# 03_-_28PINS_SCHEMATIC.net
KiCad netlist of a schematic drawn in Altium Designer
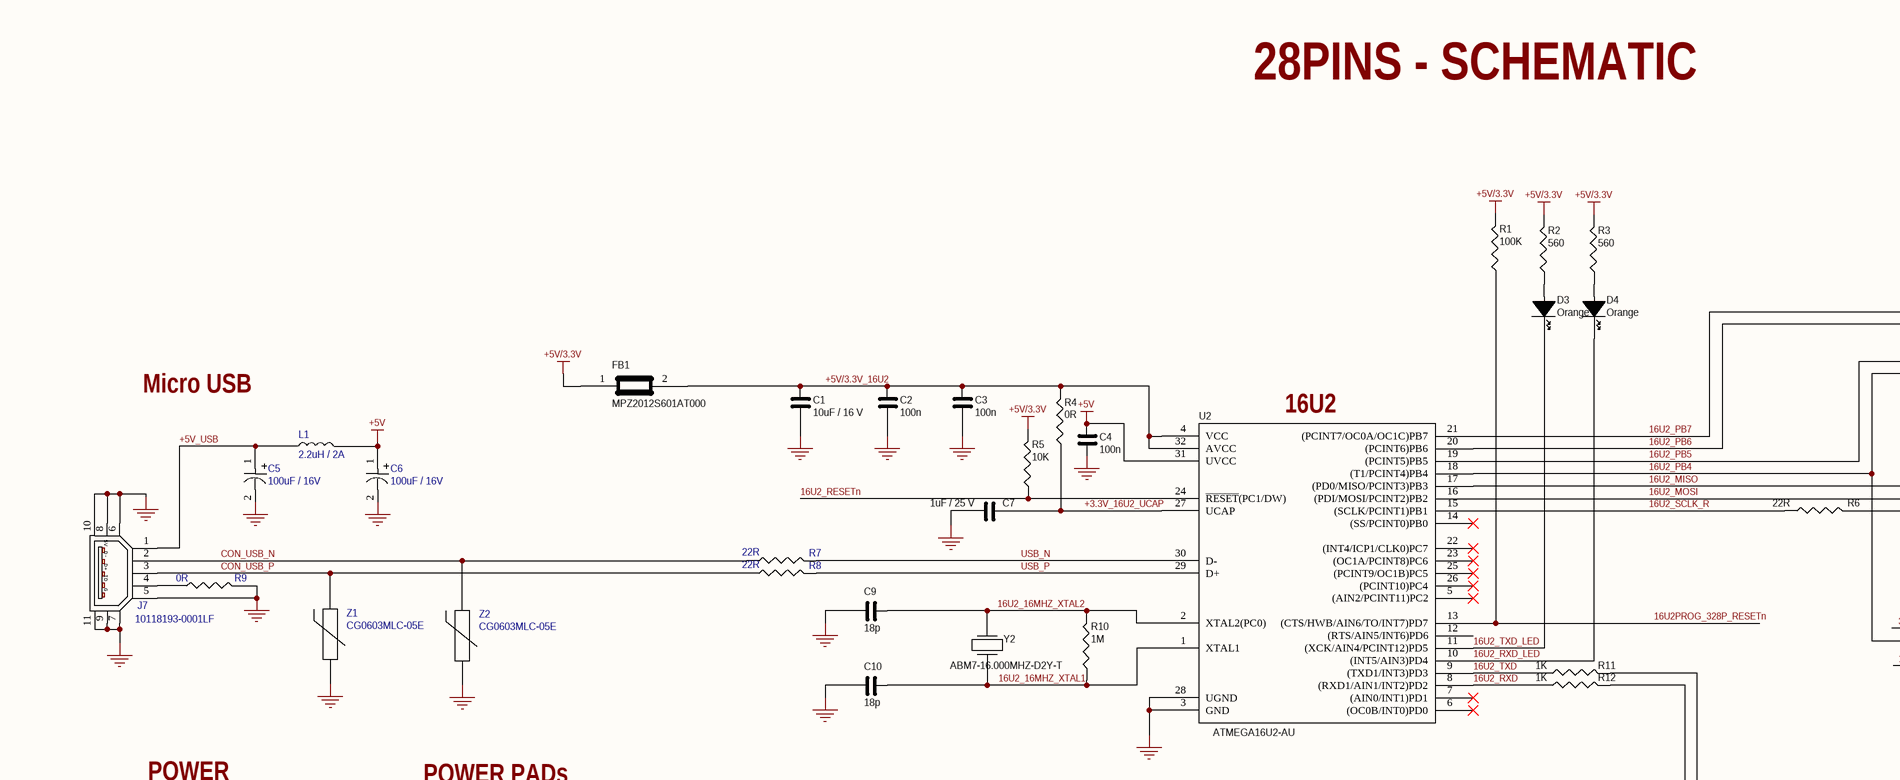
[diagram p0: [03] - 28PINS SCHEMATIC.SchDoc, top left]
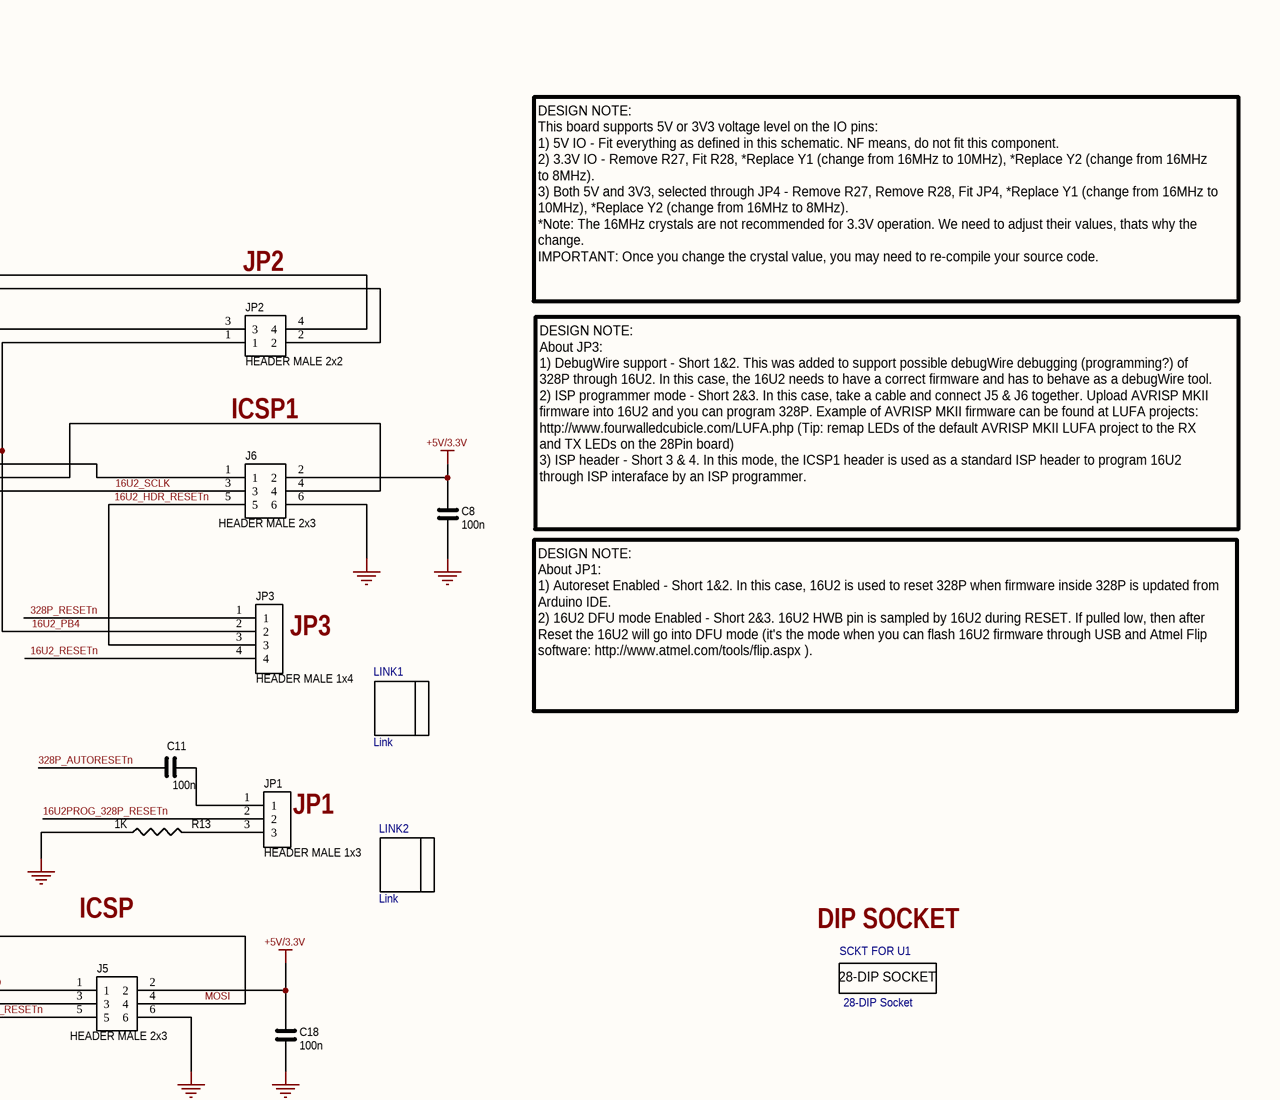
[diagram p1: [03] - 28PINS SCHEMATIC.SchDoc, top right]
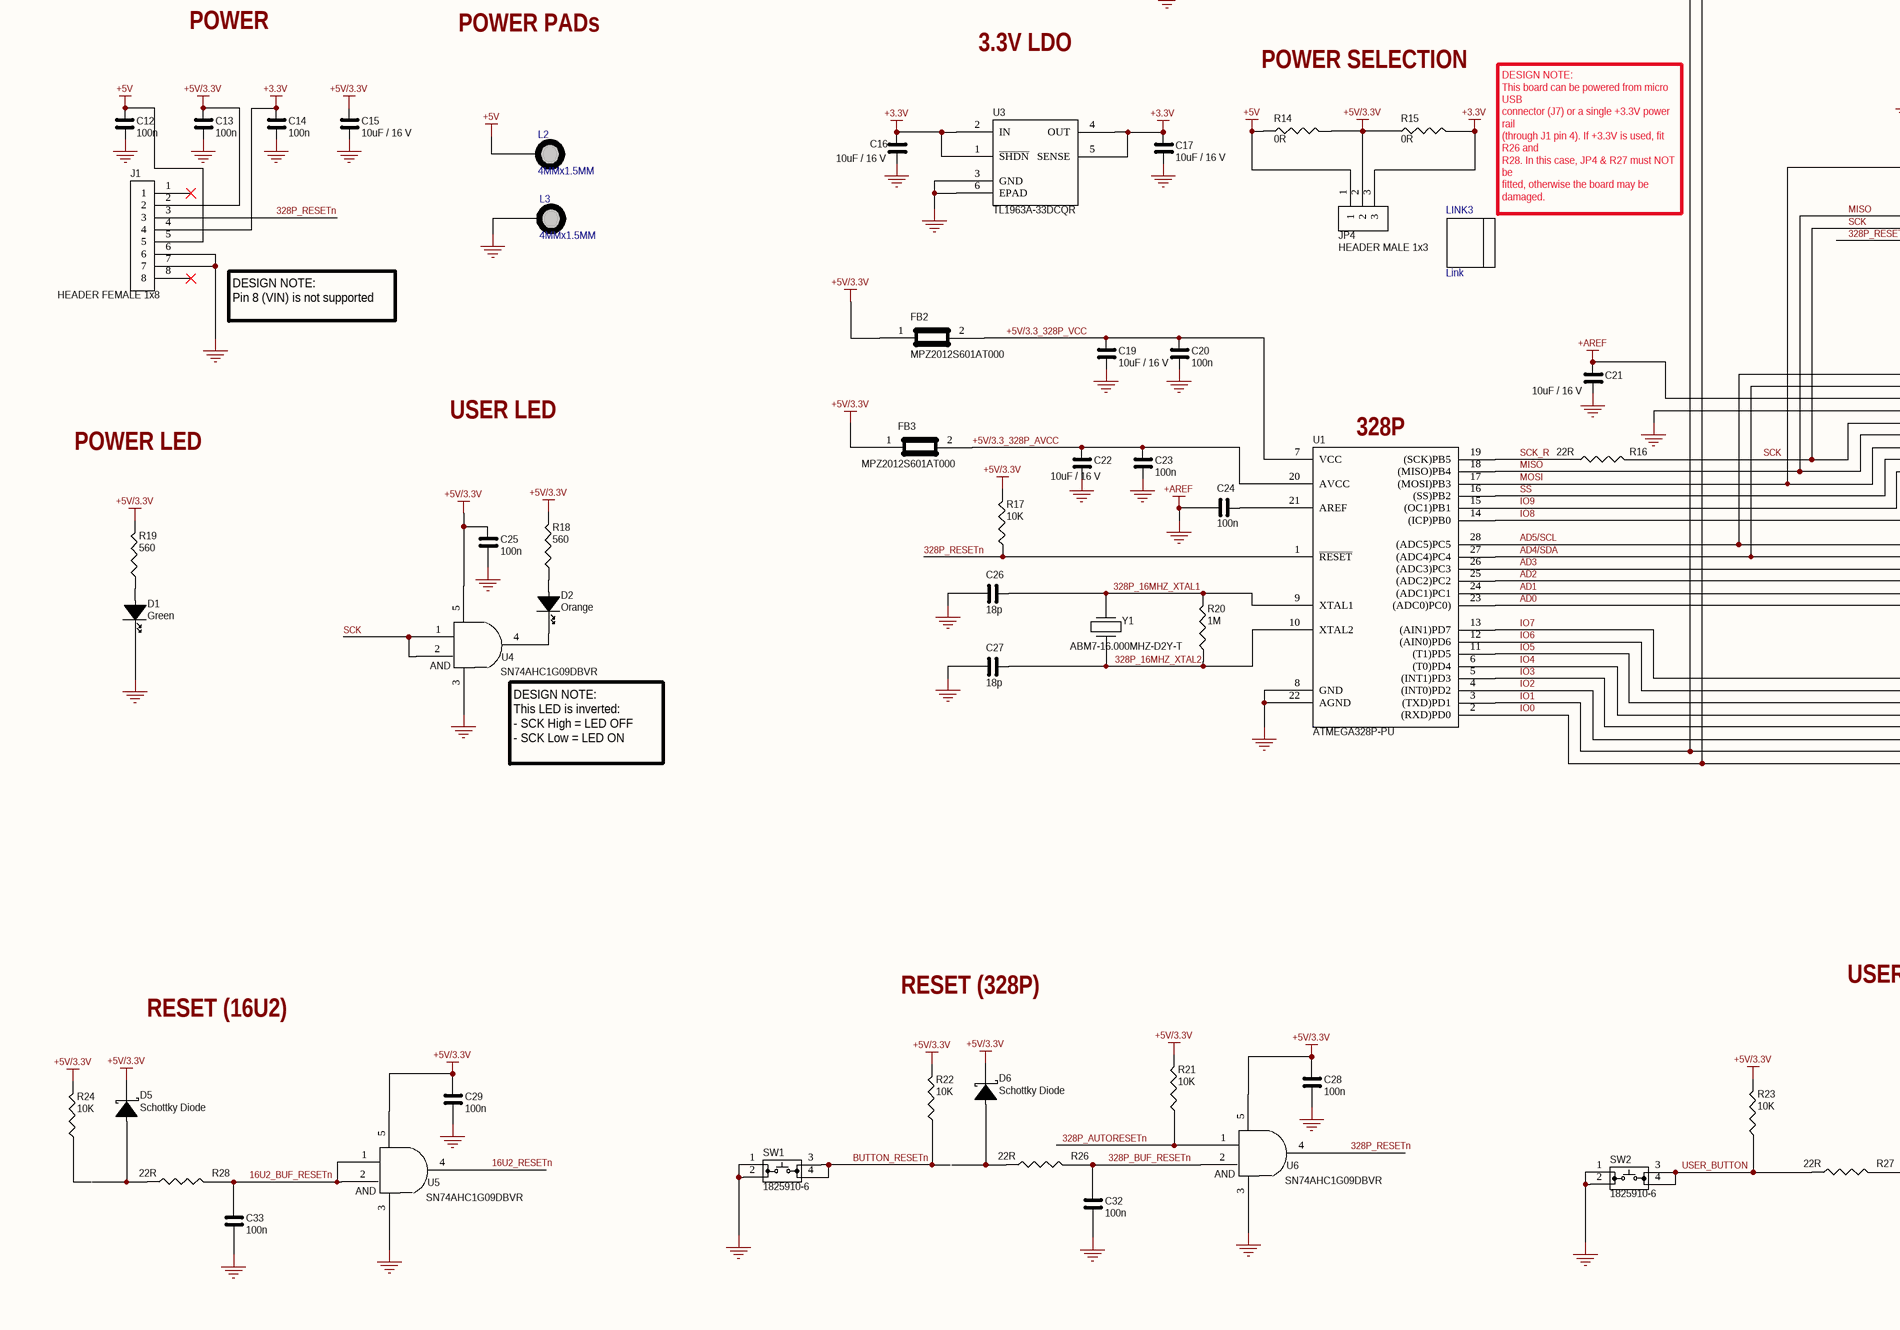
[diagram p2: [03] - 28PINS SCHEMATIC.SchDoc, bottom left]
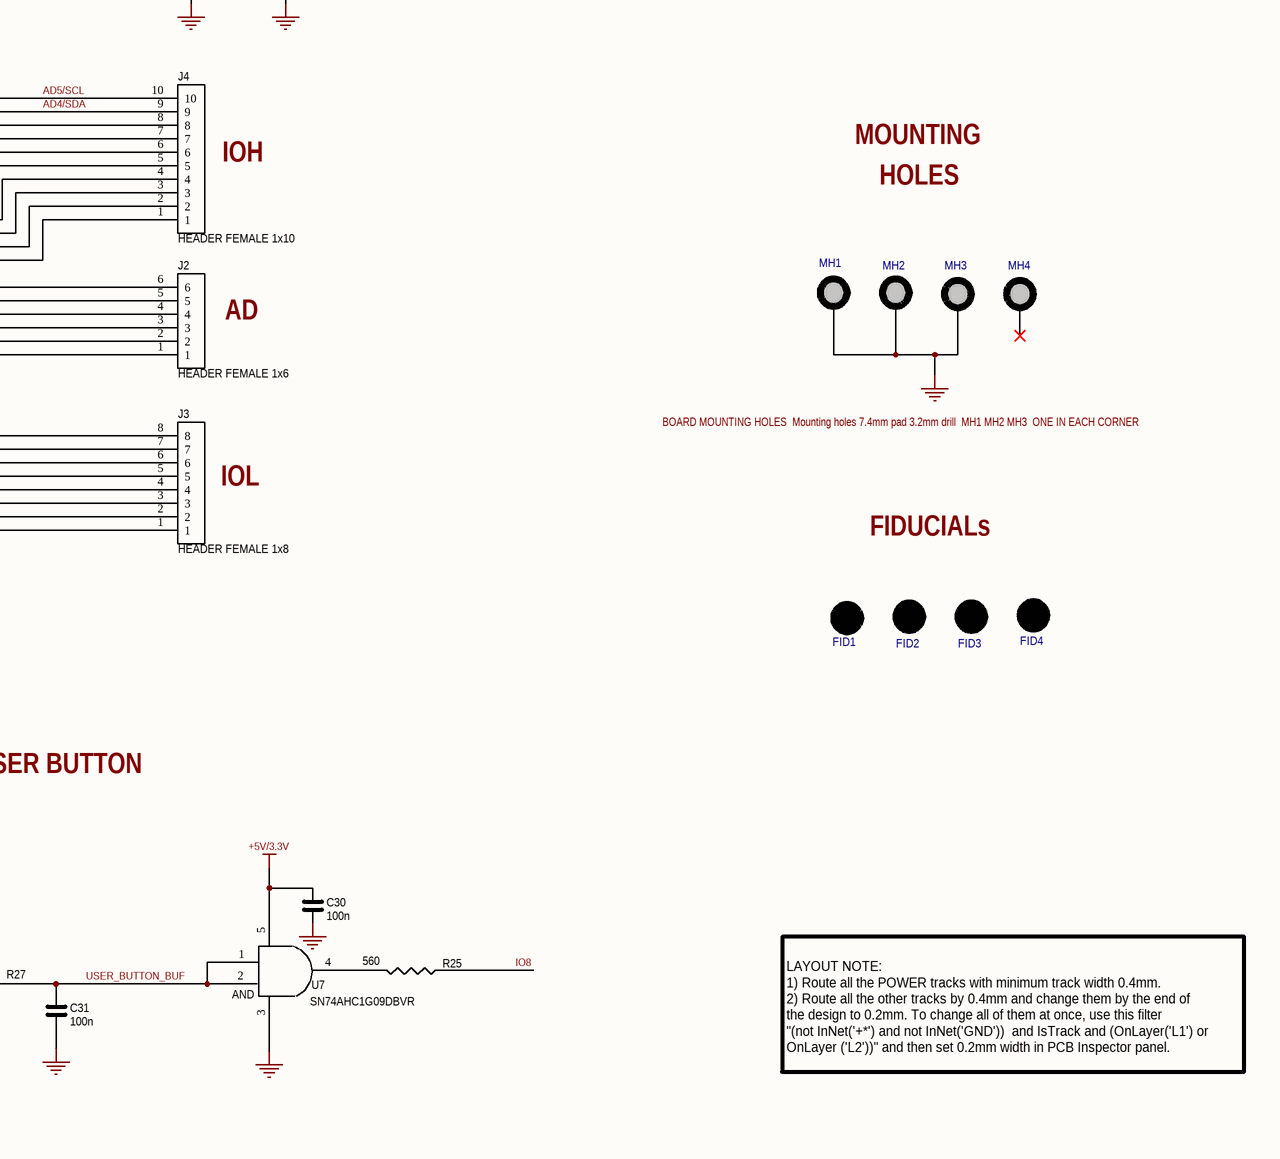
[diagram p3: [03] - 28PINS SCHEMATIC.SchDoc, bottom right]

(export (version "E")
  (design (tool "Eeschema 10.0.6"))
  (components
    (comp (ref "C1")
      (value "10uF / 16 V")
      (footprint "C0805")
      (libsource (lib "28Pins_Schematic_Lib") (part "10uF_CAP"))
    )
    (comp (ref "C2")
      (value "100n")
      (footprint "C0805")
      (libsource (lib "28Pins_Schematic_Lib") (part "0.1uF_CAP"))
    )
    (comp (ref "C3")
      (value "100n")
      (footprint "C0805")
      (libsource (lib "28Pins_Schematic_Lib") (part "0.1uF_CAP"))
    )
    (comp (ref "C4")
      (value "100n")
      (footprint "C0805")
      (libsource (lib "28Pins_Schematic_Lib") (part "0.1uF_CAP"))
    )
    (comp (ref "C5")
      (value "100uF / 16V")
      (footprint "C_ALU_C_SIZE")
      (libsource (lib "28Pins_Schematic_Lib") (part "100uF_PCAP"))
    )
    (comp (ref "C6")
      (value "100uF / 16V")
      (footprint "C_ALU_C_SIZE")
      (libsource (lib "28Pins_Schematic_Lib") (part "100uF_PCAP"))
    )
    (comp (ref "C7")
      (value "1uF / 25 V")
      (footprint "C0805")
      (libsource (lib "28Pins_Schematic_Lib") (part "1uF_CAP"))
    )
    (comp (ref "C8")
      (value "100n")
      (footprint "C0805")
      (libsource (lib "28Pins_Schematic_Lib") (part "0.1uF_CAP"))
    )
    (comp (ref "C9")
      (value "18p")
      (footprint "C0805")
      (libsource (lib "28Pins_Schematic_Lib") (part "18pF_CAP"))
    )
    (comp (ref "C10")
      (value "18p")
      (footprint "C0805")
      (libsource (lib "28Pins_Schematic_Lib") (part "18pF_CAP"))
    )
    (comp (ref "C11")
      (value "100n")
      (footprint "C0805")
      (libsource (lib "28Pins_Schematic_Lib") (part "0.1uF_CAP"))
    )
    (comp (ref "C12")
      (value "100n")
      (footprint "C0805")
      (libsource (lib "28Pins_Schematic_Lib") (part "0.1uF_CAP"))
    )
    (comp (ref "C13")
      (value "100n")
      (footprint "C0805")
      (libsource (lib "28Pins_Schematic_Lib") (part "0.1uF_CAP"))
    )
    (comp (ref "C14")
      (value "100n")
      (footprint "C0805")
      (libsource (lib "28Pins_Schematic_Lib") (part "0.1uF_CAP"))
    )
    (comp (ref "C15")
      (value "10uF / 16 V")
      (footprint "C0805")
      (libsource (lib "28Pins_Schematic_Lib") (part "10uF_CAP"))
    )
    (comp (ref "C16")
      (value "10uF / 16 V")
      (footprint "C0805")
      (libsource (lib "28Pins_Schematic_Lib") (part "10uF_CAP"))
    )
    (comp (ref "C17")
      (value "10uF / 16 V")
      (footprint "C0805")
      (libsource (lib "28Pins_Schematic_Lib") (part "10uF_CAP"))
    )
    (comp (ref "C18")
      (value "100n")
      (footprint "C0805")
      (libsource (lib "28Pins_Schematic_Lib") (part "0.1uF_CAP"))
    )
    (comp (ref "C19")
      (value "10uF / 16 V")
      (footprint "C0805")
      (libsource (lib "28Pins_Schematic_Lib") (part "10uF_CAP"))
    )
    (comp (ref "C20")
      (value "100n")
      (footprint "C0805")
      (libsource (lib "28Pins_Schematic_Lib") (part "0.1uF_CAP"))
    )
    (comp (ref "C21")
      (value "10uF / 16 V")
      (footprint "C0805")
      (libsource (lib "28Pins_Schematic_Lib") (part "10uF_CAP"))
    )
    (comp (ref "C22")
      (value "10uF / 16 V")
      (footprint "C0805")
      (libsource (lib "28Pins_Schematic_Lib") (part "10uF_CAP"))
    )
    (comp (ref "C23")
      (value "100n")
      (footprint "C0805")
      (libsource (lib "28Pins_Schematic_Lib") (part "0.1uF_CAP"))
    )
    (comp (ref "C24")
      (value "100n")
      (footprint "C0805")
      (libsource (lib "28Pins_Schematic_Lib") (part "0.1uF_CAP"))
    )
    (comp (ref "C25")
      (value "100n")
      (footprint "C0805")
      (libsource (lib "28Pins_Schematic_Lib") (part "0.1uF_CAP"))
    )
    (comp (ref "C26")
      (value "18p")
      (footprint "C0805")
      (libsource (lib "28Pins_Schematic_Lib") (part "18pF_CAP"))
    )
    (comp (ref "C27")
      (value "18p")
      (footprint "C0805")
      (libsource (lib "28Pins_Schematic_Lib") (part "18pF_CAP"))
    )
    (comp (ref "C28")
      (value "100n")
      (footprint "C0805")
      (libsource (lib "28Pins_Schematic_Lib") (part "0.1uF_CAP"))
    )
    (comp (ref "C29")
      (value "100n")
      (footprint "C0805")
      (libsource (lib "28Pins_Schematic_Lib") (part "0.1uF_CAP"))
    )
    (comp (ref "C30")
      (value "100n")
      (footprint "C0805")
      (libsource (lib "28Pins_Schematic_Lib") (part "0.1uF_CAP"))
    )
    (comp (ref "C31")
      (value "100n")
      (footprint "C0805")
      (libsource (lib "28Pins_Schematic_Lib") (part "0.1uF_CAP"))
    )
    (comp (ref "C32")
      (value "100n")
      (footprint "C0805")
      (libsource (lib "28Pins_Schematic_Lib") (part "0.1uF_CAP"))
    )
    (comp (ref "C33")
      (value "100n")
      (footprint "C0805")
      (libsource (lib "28Pins_Schematic_Lib") (part "0.1uF_CAP"))
    )
    (comp (ref "D1")
      (value "Green")
      (footprint "LED0603")
      (libsource (lib "28Pins_Schematic_Lib") (part "LED_Green"))
    )
    (comp (ref "D2")
      (value "Orange")
      (footprint "LED0603")
      (libsource (lib "28Pins_Schematic_Lib") (part "LED_Orange"))
    )
    (comp (ref "D3")
      (value "Orange")
      (footprint "LED0603")
      (libsource (lib "28Pins_Schematic_Lib") (part "LED_Orange"))
    )
    (comp (ref "D4")
      (value "Orange")
      (footprint "LED0603")
      (libsource (lib "28Pins_Schematic_Lib") (part "LED_Orange"))
    )
    (comp (ref "D5")
      (value "Schottky Diode")
      (footprint "SOD323")
      (description "Diode,Schottky Barrier,Fast,Vr 30V,If 200mA,Pkg SOD-323,Vf 0.52VDC,Trr 5ns")
      (fields
        (field (name "MANUFACTURER") "ON Semiconductor")
        (field (name "MANUFACTURER PART NUMBER") "BAT54HT1G")
      )
      (libsource (lib "28Pins_Schematic_Lib") (part "Schottky Diode"))
    )
    (comp (ref "D6")
      (value "Schottky Diode")
      (footprint "SOD323")
      (description "Diode,Schottky Barrier,Fast,Vr 30V,If 200mA,Pkg SOD-323,Vf 0.52VDC,Trr 5ns")
      (fields
        (field (name "MANUFACTURER") "ON Semiconductor")
        (field (name "MANUFACTURER PART NUMBER") "BAT54HT1G")
      )
      (libsource (lib "28Pins_Schematic_Lib") (part "Schottky Diode"))
    )
    (comp (ref "FB1")
      (value "MPZ2012S601AT000")
      (footprint "C0805")
      (libsource (lib "28Pins_Schematic_Lib") (part "Ferrite_Bead"))
    )
    (comp (ref "FB2")
      (value "MPZ2012S601AT000")
      (footprint "C0805")
      (libsource (lib "28Pins_Schematic_Lib") (part "Ferrite_Bead"))
    )
    (comp (ref "FB3")
      (value "MPZ2012S601AT000")
      (footprint "C0805")
      (libsource (lib "28Pins_Schematic_Lib") (part "Ferrite_Bead"))
    )
    (comp (ref "FID1")
      (value "FID_1mm")
      (footprint "FID_40x1120")
      (description "Fiducial 40mil diameter")
      (libsource (lib "28Pins_Schematic_Lib") (part "Fiducial"))
    )
    (comp (ref "FID2")
      (value "FID_1mm")
      (footprint "FID_40x1120")
      (description "Fiducial 40mil diameter")
      (libsource (lib "28Pins_Schematic_Lib") (part "Fiducial"))
    )
    (comp (ref "FID3")
      (value "FID_1mm")
      (footprint "FID_40x1120")
      (description "Fiducial 40mil diameter")
      (libsource (lib "28Pins_Schematic_Lib") (part "Fiducial"))
    )
    (comp (ref "FID4")
      (value "FID_1mm")
      (footprint "FID_40x1120")
      (description "Fiducial 40mil diameter")
      (libsource (lib "28Pins_Schematic_Lib") (part "Fiducial"))
    )
    (comp (ref "J1")
      (value "HEADER FEMALE 1x8")
      (footprint "8x1PIN_FEMALE_HDR")
      (libsource (lib "28Pins_Schematic_Lib") (part "8x1Pin_Female_Hdr"))
    )
    (comp (ref "J2")
      (value "HEADER FEMALE 1x6")
      (footprint "6x1PIN_FEMALE_HDR")
      (libsource (lib "28Pins_Schematic_Lib") (part "6x1Pin_Female_Hdr"))
    )
    (comp (ref "J3")
      (value "HEADER FEMALE 1x8")
      (footprint "8x1PIN_FEMALE_HDR")
      (libsource (lib "") (part "8x1Pin_Female_Hdr_1"))
    )
    (comp (ref "J4")
      (value "HEADER FEMALE 1x10")
      (footprint "10x1PIN_FEMALE_HDR")
      (libsource (lib "28Pins_Schematic_Lib") (part "10Pin_Female_Hdr"))
    )
    (comp (ref "J5")
      (value "HEADER MALE 2x3")
      (footprint "2x3PIN_MALE_HDR")
      (libsource (lib "28Pins_Schematic_Lib") (part "2x3Pin_Male_Hdr"))
    )
    (comp (ref "J6")
      (value "HEADER MALE 2x3")
      (footprint "2x3PIN_MALE_HDR")
      (libsource (lib "28Pins_Schematic_Lib") (part "2x3Pin_Male_Hdr"))
    )
    (comp (ref "J7")
      (value "10118193-0001LF")
      (footprint "USB_SOP")
      (description "Right Angle Surface Mount Mount Female USB Connector 100 V ac 1.8A")
      (fields (field (name "MANUFACTURER") "Amphenol ICC"))
      (libsource (lib "28Pins_Schematic_Lib") (part "10118193-0001LF"))
    )
    (comp (ref "JP1")
      (value "HEADER MALE 1x3")
      (footprint "1x3PIN_MALE_HDR")
      (libsource (lib "28Pins_Schematic_Lib") (part "1x3Pin_Male_Hdr"))
    )
    (comp (ref "JP2")
      (value "HEADER MALE 2x2")
      (footprint "2x2PIN_MALE_HDR")
      (libsource (lib "28Pins_Schematic_Lib") (part "2x2Pin_Male_Hdr"))
    )
    (comp (ref "JP3")
      (value "HEADER MALE 1x4")
      (footprint "1x4PIN_MALE_HDR")
      (libsource (lib "28Pins_Schematic_Lib") (part "1x4Pin_Male_Hdr"))
    )
    (comp (ref "JP4")
      (value "HEADER MALE 1x3")
      (footprint "1x3PIN_MALE_HDR")
      (libsource (lib "") (part "1x3Pin_Male_Hdr_1"))
    )
    (comp (ref "L1")
      (value "2.2uH / 2A")
      (footprint "L1210")
      (description "Inductor")
      (libsource (lib "28Pins_Schematic_Lib") (part "L1210R2R2MDWIT"))
    )
    (comp (ref "L2")
      (value "4MMx1.5MM")
      (footprint "PADS_WITH_WHOLE_4mmx1.5mm")
      (libsource (lib "28Pins_Schematic_Lib") (part "PAD_WITH_WHOLE_4MMx1.5MM"))
    )
    (comp (ref "L3")
      (value "4MMx1.5MM")
      (footprint "PADS_WITH_WHOLE_4mmx1.5mm")
      (libsource (lib "28Pins_Schematic_Lib") (part "PAD_WITH_WHOLE_4MMx1.5MM"))
    )
    (comp (ref "LINK1")
      (value "Link")
      (description "CONN JUMPER")
      (libsource (lib "28Pins_Schematic_Lib") (part "Link"))
    )
    (comp (ref "LINK2")
      (value "Link")
      (description "CONN JUMPER")
      (libsource (lib "28Pins_Schematic_Lib") (part "Link"))
    )
    (comp (ref "LINK3")
      (value "Link")
      (description "CONN JUMPER")
      (libsource (lib "28Pins_Schematic_Lib") (part "Link"))
    )
    (comp (ref "MH1")
      (value "Mounting Whole 3.4mmx3.2mm")
      (footprint "MOUNTING_WHOLE_NON_COPPER")
      (libsource (lib "28Pins_Schematic_Lib") (part "MOUNTING_WHOLE_NON_COPPER"))
    )
    (comp (ref "MH2")
      (value "Mounting Whole 3.4mmx3.2mm")
      (footprint "MOUNTING_WHOLE_NON_COPPER")
      (libsource (lib "28Pins_Schematic_Lib") (part "MOUNTING_WHOLE_NON_COPPER"))
    )
    (comp (ref "MH3")
      (value "Mounting Whole 3.4mmx3.2mm")
      (footprint "MOUNTING_WHOLE_NON_COPPER")
      (libsource (lib "28Pins_Schematic_Lib") (part "MOUNTING_WHOLE_NON_COPPER"))
    )
    (comp (ref "MH4")
      (value "Mounting Whole 3.4mmx3.2mm")
      (footprint "MOUNTING_WHOLE_NON_COPPER")
      (libsource (lib "28Pins_Schematic_Lib") (part "MOUNTING_WHOLE_NON_COPPER"))
    )
    (comp (ref "R1")
      (value "100K")
      (footprint "R0805")
      (libsource (lib "28Pins_Schematic_Lib") (part "100K_Resistor"))
    )
    (comp (ref "R2")
      (value "560")
      (footprint "R0805")
      (libsource (lib "28Pins_Schematic_Lib") (part "560_Resistor"))
    )
    (comp (ref "R3")
      (value "560")
      (footprint "R0805")
      (libsource (lib "28Pins_Schematic_Lib") (part "560_Resistor"))
    )
    (comp (ref "R4")
      (value "0R")
      (footprint "R0805")
      (libsource (lib "28Pins_Schematic_Lib") (part "0R_Resistor"))
    )
    (comp (ref "R5")
      (value "10K")
      (footprint "R0805")
      (libsource (lib "28Pins_Schematic_Lib") (part "10K_Resistor"))
    )
    (comp (ref "R6")
      (value "22R")
      (footprint "R0805")
      (libsource (lib "28Pins_Schematic_Lib") (part "22_Resistor"))
    )
    (comp (ref "R7")
      (value "22R")
      (footprint "R0805")
      (libsource (lib "28Pins_Schematic_Lib") (part "22_Resistor"))
    )
    (comp (ref "R8")
      (value "22R")
      (footprint "R0805")
      (libsource (lib "28Pins_Schematic_Lib") (part "22_Resistor"))
    )
    (comp (ref "R9")
      (value "0R")
      (footprint "R0805")
      (libsource (lib "28Pins_Schematic_Lib") (part "0R_Resistor"))
    )
    (comp (ref "R10")
      (value "1M")
      (footprint "R0805")
      (libsource (lib "28Pins_Schematic_Lib") (part "1M_Resistor"))
    )
    (comp (ref "R11")
      (value "1K")
      (footprint "R0805")
      (libsource (lib "28Pins_Schematic_Lib") (part "1K_Resistor"))
    )
    (comp (ref "R12")
      (value "1K")
      (footprint "R0805")
      (libsource (lib "28Pins_Schematic_Lib") (part "1K_Resistor"))
    )
    (comp (ref "R13")
      (value "1K")
      (footprint "R0805")
      (libsource (lib "28Pins_Schematic_Lib") (part "1K_Resistor"))
    )
    (comp (ref "R14")
      (value "0R")
      (footprint "R0805")
      (libsource (lib "28Pins_Schematic_Lib") (part "0R_Resistor"))
    )
    (comp (ref "R15")
      (value "0R")
      (footprint "R0805")
      (libsource (lib "28Pins_Schematic_Lib") (part "0R_Resistor"))
    )
    (comp (ref "R16")
      (value "22R")
      (footprint "R0805")
      (libsource (lib "28Pins_Schematic_Lib") (part "22_Resistor"))
    )
    (comp (ref "R17")
      (value "10K")
      (footprint "R0805")
      (libsource (lib "28Pins_Schematic_Lib") (part "10K_Resistor"))
    )
    (comp (ref "R18")
      (value "560")
      (footprint "R0805")
      (libsource (lib "28Pins_Schematic_Lib") (part "560_Resistor"))
    )
    (comp (ref "R19")
      (value "560")
      (footprint "R0805")
      (libsource (lib "28Pins_Schematic_Lib") (part "560_Resistor"))
    )
    (comp (ref "R20")
      (value "1M")
      (footprint "R0805")
      (libsource (lib "28Pins_Schematic_Lib") (part "1M_Resistor"))
    )
    (comp (ref "R21")
      (value "10K")
      (footprint "R0805")
      (libsource (lib "28Pins_Schematic_Lib") (part "10K_Resistor"))
    )
    (comp (ref "R22")
      (value "10K")
      (footprint "R0805")
      (libsource (lib "28Pins_Schematic_Lib") (part "10K_Resistor"))
    )
    (comp (ref "R23")
      (value "10K")
      (footprint "R0805")
      (libsource (lib "28Pins_Schematic_Lib") (part "10K_Resistor"))
    )
    (comp (ref "R24")
      (value "10K")
      (footprint "R0805")
      (libsource (lib "28Pins_Schematic_Lib") (part "10K_Resistor"))
    )
    (comp (ref "R25")
      (value "560")
      (footprint "R0805")
      (libsource (lib "28Pins_Schematic_Lib") (part "560_Resistor"))
    )
    (comp (ref "R26")
      (value "22R")
      (footprint "R0805")
      (libsource (lib "28Pins_Schematic_Lib") (part "22_Resistor"))
    )
    (comp (ref "R27")
      (value "22R")
      (footprint "R0805")
      (libsource (lib "28Pins_Schematic_Lib") (part "22_Resistor"))
    )
    (comp (ref "R28")
      (value "22R")
      (footprint "R0805")
      (libsource (lib "28Pins_Schematic_Lib") (part "22_Resistor"))
    )
    (comp (ref "SCKT FOR U1")
      (value "28-DIP Socket")
      (footprint "28-DIP_SCKT")
      (libsource (lib "28Pins_Schematic_Lib") (part "28Pin_DIP"))
    )
    (comp (ref "SW1")
      (value "1825910-6")
      (footprint "4PIN_BUTTON")
      (description "Push_Button")
      (libsource (lib "28Pins_Schematic_Lib") (part "4Pin_Push_Button"))
    )
    (comp (ref "SW2")
      (value "1825910-6")
      (footprint "4PIN_BUTTON")
      (description "Push_Button")
      (libsource (lib "28Pins_Schematic_Lib") (part "4Pin_Push_Button"))
    )
    (comp (ref "U1")
      (value "ATMEGA328P-PU")
      (footprint "28_DIP_U1")
      (description "ATMEGA328P-PU; 8 bit Microcontroller AVR 20MHz 1; 32kb Flash; 2kb RAM; I2C SPI 2")
      (fields (field (name "MANUFACTURER") "Microchip Technology Inc."))
      (libsource (lib "28Pins_Schematic_Lib") (part "ATMEGA328P-PU"))
    )
    (comp (ref "U2")
      (value "ATMEGA16U2-AU")
      (footprint "TQFP32")
      (libsource (lib "28Pins_Schematic_Lib") (part "ATMEGA16U2-AU"))
    )
    (comp (ref "U3")
      (value "TL1963A-33DCQR")
      (footprint "DCQR R-PDSO-G6")
      (libsource (lib "28Pins_Schematic_Lib") (part "Regulator"))
    )
    (comp (ref "U4")
      (value "SN74AHC1G09DBVR")
      (footprint "DBV_SOP_23_5")
      (libsource (lib "28Pins_Schematic_Lib") (part "AND gate"))
    )
    (comp (ref "U5")
      (value "SN74AHC1G09DBVR")
      (footprint "DBV_SOP_23_5")
      (libsource (lib "28Pins_Schematic_Lib") (part "AND gate"))
    )
    (comp (ref "U6")
      (value "SN74AHC1G09DBVR")
      (footprint "DBV_SOP_23_5")
      (libsource (lib "28Pins_Schematic_Lib") (part "AND gate"))
    )
    (comp (ref "U7")
      (value "SN74AHC1G09DBVR")
      (footprint "DBV_SOP_23_5")
      (libsource (lib "28Pins_Schematic_Lib") (part "AND gate"))
    )
    (comp (ref "Y1")
      (value "ABM7-16.000MHZ-D2Y-T")
      (footprint "AMB7_V1")
      (description "Crystal; Ceramic; 16.000MHZ; 18pf; 20ppm @ 25C; 30ppm -40+85C; 6.0 x 3.5 x 1.2mm; T/R")
      (fields (field (name "MANUFACTURER") "Abracon"))
      (libsource (lib "28Pins_Schematic_Lib") (part "ABM7-16.000MHZ-D2Y-T"))
    )
    (comp (ref "Y2")
      (value "ABM7-16.000MHZ-D2Y-T")
      (footprint "AMB7_V1")
      (description "Crystal; Ceramic; 16.000MHZ; 18pf; 20ppm @ 25C; 30ppm -40+85C; 6.0 x 3.5 x 1.2mm; T/R")
      (fields (field (name "MANUFACTURER") "Abracon"))
      (libsource (lib "28Pins_Schematic_Lib") (part "ABM7-16.000MHZ-D2Y-T"))
    )
    (comp (ref "Z1")
      (value "CG0603MLC-05E")
      (footprint "R0603")
      (description "Varistor; ESD Clamp Protector; 5 VDC; 20 Vclamp; IEC 61000-4-2 Level 4; 0603 SMD")
      (fields (field (name "MANUFACTURER") "Bourns"))
      (libsource (lib "28Pins_Schematic_Lib") (part "CG0603MLC-05E"))
    )
    (comp (ref "Z2")
      (value "CG0603MLC-05E")
      (footprint "R0603")
      (description "Varistor; ESD Clamp Protector; 5 VDC; 20 Vclamp; IEC 61000-4-2 Level 4; 0603 SMD")
      (fields (field (name "MANUFACTURER") "Bourns"))
      (libsource (lib "28Pins_Schematic_Lib") (part "CG0603MLC-05E"))
    )
  )
  (nets
    (net (code "1") (name "+3.3V") (class "Default")
      (node (ref "C14") (pin "2") (pinfunction "2_2") (pintype "passive"))
      (node (ref "C16") (pin "2") (pinfunction "2_2") (pintype "passive"))
      (node (ref "C17") (pin "2") (pinfunction "2_2") (pintype "passive"))
      (node (ref "J1") (pin "4") (pinfunction "4_4") (pintype "passive"))
      (node (ref "JP4") (pin "3") (pinfunction "3_3") (pintype "passive"))
      (node (ref "R15") (pin "2") (pinfunction "2_2") (pintype "passive"))
      (node (ref "U3") (pin "1") (pinfunction "~{SHDN}_1") (pintype "passive"))
      (node (ref "U3") (pin "2") (pinfunction "IN_2") (pintype "passive"))
      (node (ref "U3") (pin "4") (pinfunction "OUT_4") (pintype "passive"))
      (node (ref "U3") (pin "5") (pinfunction "SENSE_5") (pintype "passive"))
    )
    (net (code "2") (name "+5V") (class "Default")
      (node (ref "C12") (pin "1") (pinfunction "1_1") (pintype "passive"))
      (node (ref "C4") (pin "2") (pinfunction "2_2") (pintype "passive"))
      (node (ref "C6") (pin "1") (pinfunction "1_1") (pintype "passive"))
      (node (ref "J1") (pin "5") (pinfunction "5_5") (pintype "passive"))
      (node (ref "JP4") (pin "1") (pinfunction "1_1") (pintype "passive"))
      (node (ref "L1") (pin "2") (pinfunction "2_2") (pintype "passive"))
      (node (ref "L2") (pin "1") (pinfunction "1_1") (pintype "passive"))
      (node (ref "R14") (pin "1") (pinfunction "1_1") (pintype "passive"))
      (node (ref "U2") (pin "31") (pinfunction "UVCC_31") (pintype "passive"))
    )
    (net (code "3") (name "+5V{slash}3.3V") (class "Default")
      (node (ref "C13") (pin "2") (pinfunction "2_2") (pintype "passive"))
      (node (ref "C15") (pin "2") (pinfunction "2_2") (pintype "passive"))
      (node (ref "C18") (pin "2") (pinfunction "2_2") (pintype "passive"))
      (node (ref "C25") (pin "2") (pinfunction "2_2") (pintype "passive"))
      (node (ref "C28") (pin "2") (pinfunction "2_2") (pintype "passive"))
      (node (ref "C29") (pin "2") (pinfunction "2_2") (pintype "passive"))
      (node (ref "C30") (pin "2") (pinfunction "2_2") (pintype "passive"))
      (node (ref "C8") (pin "2") (pinfunction "2_2") (pintype "passive"))
      (node (ref "D5") (pin "1") (pinfunction "Cathode_1") (pintype "passive"))
      (node (ref "D6") (pin "1") (pinfunction "Cathode_1") (pintype "passive"))
      (node (ref "FB1") (pin "1") (pinfunction "1_1") (pintype "passive"))
      (node (ref "FB2") (pin "1") (pinfunction "1_1") (pintype "passive"))
      (node (ref "FB3") (pin "1") (pinfunction "1_1") (pintype "passive"))
      (node (ref "J1") (pin "2") (pinfunction "2_2") (pintype "passive"))
      (node (ref "J5") (pin "2") (pinfunction "2_2") (pintype "passive"))
      (node (ref "J6") (pin "2") (pinfunction "2_2") (pintype "passive"))
      (node (ref "JP4") (pin "2") (pinfunction "2_2") (pintype "passive"))
      (node (ref "R1") (pin "2") (pinfunction "2_2") (pintype "passive"))
      (node (ref "R14") (pin "2") (pinfunction "2_2") (pintype "passive"))
      (node (ref "R15") (pin "1") (pinfunction "1_1") (pintype "passive"))
      (node (ref "R17") (pin "2") (pinfunction "2_2") (pintype "passive"))
      (node (ref "R18") (pin "2") (pinfunction "2_2") (pintype "passive"))
      (node (ref "R19") (pin "2") (pinfunction "2_2") (pintype "passive"))
      (node (ref "R2") (pin "2") (pinfunction "2_2") (pintype "passive"))
      (node (ref "R21") (pin "2") (pinfunction "2_2") (pintype "passive"))
      (node (ref "R22") (pin "2") (pinfunction "2_2") (pintype "passive"))
      (node (ref "R23") (pin "2") (pinfunction "2_2") (pintype "passive"))
      (node (ref "R24") (pin "2") (pinfunction "2_2") (pintype "passive"))
      (node (ref "R3") (pin "2") (pinfunction "2_2") (pintype "passive"))
      (node (ref "R5") (pin "2") (pinfunction "2_2") (pintype "passive"))
      (node (ref "U4") (pin "5") (pinfunction "5_5") (pintype "passive"))
      (node (ref "U5") (pin "5") (pinfunction "5_5") (pintype "passive"))
      (node (ref "U6") (pin "5") (pinfunction "5_5") (pintype "passive"))
      (node (ref "U7") (pin "5") (pinfunction "5_5") (pintype "passive"))
    )
    (net (code "4") (name "+AREF") (class "Default")
      (node (ref "C1") (pin "1") (pinfunction "1_1") (pintype "passive"))
      (node (ref "C10") (pin "1") (pinfunction "1_1") (pintype "passive"))
      (node (ref "C12") (pin "2") (pinfunction "2_2") (pintype "passive"))
      (node (ref "C13") (pin "1") (pinfunction "1_1") (pintype "passive"))
      (node (ref "C14") (pin "1") (pinfunction "1_1") (pintype "passive"))
      (node (ref "C15") (pin "1") (pinfunction "1_1") (pintype "passive"))
      (node (ref "C16") (pin "1") (pinfunction "1_1") (pintype "passive"))
      (node (ref "C17") (pin "1") (pinfunction "1_1") (pintype "passive"))
      (node (ref "C18") (pin "1") (pinfunction "1_1") (pintype "passive"))
      (node (ref "C19") (pin "1") (pinfunction "1_1") (pintype "passive"))
      (node (ref "C2") (pin "1") (pinfunction "1_1") (pintype "passive"))
      (node (ref "C20") (pin "1") (pinfunction "1_1") (pintype "passive"))
      (node (ref "C21") (pin "1") (pinfunction "1_1") (pintype "passive"))
      (node (ref "C21") (pin "2") (pinfunction "2_2") (pintype "passive"))
      (node (ref "C22") (pin "1") (pinfunction "1_1") (pintype "passive"))
      (node (ref "C23") (pin "1") (pinfunction "1_1") (pintype "passive"))
      (node (ref "C24") (pin "2") (pinfunction "2_2") (pintype "passive"))
      (node (ref "C25") (pin "1") (pinfunction "1_1") (pintype "passive"))
      (node (ref "C26") (pin "1") (pinfunction "1_1") (pintype "passive"))
      (node (ref "C27") (pin "1") (pinfunction "1_1") (pintype "passive"))
      (node (ref "C28") (pin "1") (pinfunction "1_1") (pintype "passive"))
      (node (ref "C29") (pin "1") (pinfunction "1_1") (pintype "passive"))
      (node (ref "C3") (pin "1") (pinfunction "1_1") (pintype "passive"))
      (node (ref "C30") (pin "1") (pinfunction "1_1") (pintype "passive"))
      (node (ref "C31") (pin "1") (pinfunction "1_1") (pintype "passive"))
      (node (ref "C32") (pin "1") (pinfunction "1_1") (pintype "passive"))
      (node (ref "C33") (pin "1") (pinfunction "1_1") (pintype "passive"))
      (node (ref "C4") (pin "1") (pinfunction "1_1") (pintype "passive"))
      (node (ref "C5") (pin "2") (pinfunction "2_2") (pintype "passive"))
      (node (ref "C6") (pin "2") (pinfunction "2_2") (pintype "passive"))
      (node (ref "C7") (pin "1") (pinfunction "1_1") (pintype "passive"))
      (node (ref "C8") (pin "1") (pinfunction "1_1") (pintype "passive"))
      (node (ref "C9") (pin "1") (pinfunction "1_1") (pintype "passive"))
      (node (ref "D1") (pin "1") (pinfunction "Cathode_1") (pintype "passive"))
      (node (ref "J1") (pin "6") (pinfunction "6_6") (pintype "passive"))
      (node (ref "J1") (pin "7") (pinfunction "7_7") (pintype "passive"))
      (node (ref "J4") (pin "7") (pinfunction "7_7") (pintype "passive"))
      (node (ref "J4") (pin "8") (pinfunction "8_8") (pintype "passive"))
      (node (ref "J5") (pin "6") (pinfunction "6_6") (pintype "passive"))
      (node (ref "J6") (pin "6") (pinfunction "6_6") (pintype "passive"))
      (node (ref "J7") (pin "10") (pinfunction "10_10") (pintype "passive"))
      (node (ref "J7") (pin "11") (pinfunction "11_11") (pintype "passive"))
      (node (ref "J7") (pin "5") (pinfunction "5_5") (pintype "passive"))
      (node (ref "J7") (pin "6") (pinfunction "6_6") (pintype "passive"))
      (node (ref "J7") (pin "7") (pinfunction "7_7") (pintype "passive"))
      (node (ref "J7") (pin "8") (pinfunction "8_8") (pintype "passive"))
      (node (ref "J7") (pin "9") (pinfunction "9_9") (pintype "passive"))
      (node (ref "L3") (pin "1") (pinfunction "1_1") (pintype "passive"))
      (node (ref "MH1") (pin "1") (pinfunction "1_1") (pintype "passive"))
      (node (ref "MH2") (pin "1") (pinfunction "1_1") (pintype "passive"))
      (node (ref "MH3") (pin "1") (pinfunction "1_1") (pintype "passive"))
      (node (ref "R13") (pin "1") (pinfunction "1_1") (pintype "passive"))
      (node (ref "R9") (pin "2") (pinfunction "2_2") (pintype "passive"))
      (node (ref "SW1") (pin "1") (pinfunction "1_1") (pintype "passive"))
      (node (ref "SW1") (pin "2") (pinfunction "2_2") (pintype "passive"))
      (node (ref "SW2") (pin "1") (pinfunction "1_1") (pintype "passive"))
      (node (ref "SW2") (pin "2") (pinfunction "2_2") (pintype "passive"))
      (node (ref "U1") (pin "22") (pinfunction "AGND_22") (pintype "passive"))
      (node (ref "U1") (pin "8") (pinfunction "GND_8") (pintype "passive"))
      (node (ref "U2") (pin "28") (pinfunction "UGND_28") (pintype "passive"))
      (node (ref "U2") (pin "3") (pinfunction "GND_3") (pintype "passive"))
      (node (ref "U3") (pin "3") (pinfunction "GND_3") (pintype "passive"))
      (node (ref "U3") (pin "6") (pinfunction "EPAD_6") (pintype "passive"))
      (node (ref "U4") (pin "3") (pinfunction "3_3") (pintype "passive"))
      (node (ref "U5") (pin "3") (pinfunction "3_3") (pintype "passive"))
      (node (ref "U6") (pin "3") (pinfunction "3_3") (pintype "passive"))
      (node (ref "U7") (pin "3") (pinfunction "3_3") (pintype "passive"))
      (node (ref "Z1") (pin "1") (pinfunction "1_1") (pintype "passive"))
      (node (ref "Z2") (pin "1") (pinfunction "1_1") (pintype "passive"))
    )
    (net (code "5") (name "/+3.3V_16U2_UCAP") (class "Default")
      (node (ref "C7") (pin "2") (pinfunction "2_2") (pintype "passive"))
      (node (ref "R4") (pin "1") (pinfunction "1_1") (pintype "passive"))
      (node (ref "U2") (pin "27") (pinfunction "UCAP_27") (pintype "passive"))
    )
    (net (code "6") (name "/+5V_USB") (class "Default")
      (node (ref "C5") (pin "1") (pinfunction "1_1") (pintype "passive"))
      (node (ref "J7") (pin "1") (pinfunction "1_1") (pintype "passive"))
      (node (ref "L1") (pin "1") (pinfunction "1_1") (pintype "passive"))
    )
    (net (code "7") (name "/+5V{slash}3.3V_16U2") (class "Default")
      (node (ref "C1") (pin "2") (pinfunction "2_2") (pintype "passive"))
      (node (ref "C2") (pin "2") (pinfunction "2_2") (pintype "passive"))
      (node (ref "C3") (pin "2") (pinfunction "2_2") (pintype "passive"))
      (node (ref "FB1") (pin "2") (pinfunction "2_2") (pintype "passive"))
      (node (ref "R4") (pin "2") (pinfunction "2_2") (pintype "passive"))
      (node (ref "U2") (pin "32") (pinfunction "AVCC_32") (pintype "passive"))
      (node (ref "U2") (pin "4") (pinfunction "VCC_4") (pintype "passive"))
    )
    (net (code "8") (name "/+5V{slash}3.3_328P_AVCC") (class "Default")
      (node (ref "C22") (pin "2") (pinfunction "2_2") (pintype "passive"))
      (node (ref "C23") (pin "2") (pinfunction "2_2") (pintype "passive"))
      (node (ref "FB3") (pin "2") (pinfunction "2_2") (pintype "passive"))
      (node (ref "U1") (pin "20") (pinfunction "AVCC_20") (pintype "passive"))
    )
    (net (code "9") (name "/+5V{slash}3.3_328P_VCC") (class "Default")
      (node (ref "C19") (pin "2") (pinfunction "2_2") (pintype "passive"))
      (node (ref "C20") (pin "2") (pinfunction "2_2") (pintype "passive"))
      (node (ref "FB2") (pin "2") (pinfunction "2_2") (pintype "passive"))
      (node (ref "U1") (pin "7") (pinfunction "VCC_7") (pintype "passive"))
    )
    (net (code "10") (name "/16U2PROG_328P_RESETn") (class "Default")
      (node (ref "JP1") (pin "2") (pinfunction "2_2") (pintype "passive"))
      (node (ref "R1") (pin "1") (pinfunction "1_1") (pintype "passive"))
      (node (ref "U2") (pin "13") (pinfunction "(CTS/HWB/AIN6/TO/INT7)PD7_13") (pintype "passive"))
    )
    (net (code "11") (name "/16U2_16MHZ_XTAL1") (class "Default")
      (node (ref "C10") (pin "2") (pinfunction "2_2") (pintype "passive"))
      (node (ref "R10") (pin "1") (pinfunction "1_1") (pintype "passive"))
      (node (ref "U2") (pin "1") (pinfunction "XTAL1_1") (pintype "passive"))
      (node (ref "Y2") (pin "1") (pinfunction "1_1") (pintype "passive"))
    )
    (net (code "12") (name "/16U2_16MHZ_XTAL2") (class "Default")
      (node (ref "C9") (pin "2") (pinfunction "2_2") (pintype "passive"))
      (node (ref "R10") (pin "2") (pinfunction "2_2") (pintype "passive"))
      (node (ref "U2") (pin "2") (pinfunction "XTAL2(PC0)_2") (pintype "passive"))
      (node (ref "Y2") (pin "2") (pinfunction "2_2") (pintype "passive"))
    )
    (net (code "13") (name "/16U2_BUF_RESETn") (class "Default")
      (node (ref "C33") (pin "2") (pinfunction "2_2") (pintype "passive"))
      (node (ref "R28") (pin "2") (pinfunction "2_2") (pintype "passive"))
      (node (ref "U5") (pin "1") (pinfunction "1_1") (pintype "passive"))
      (node (ref "U5") (pin "2") (pinfunction "2_2") (pintype "passive"))
    )
    (net (code "14") (name "/16U2_HDR_RESETn") (class "Default")
      (node (ref "J6") (pin "5") (pinfunction "5_5") (pintype "passive"))
      (node (ref "JP3") (pin "3") (pinfunction "3_3") (pintype "passive"))
    )
    (net (code "15") (name "/16U2_MISO") (class "Default")
      (node (ref "J6") (pin "1") (pinfunction "1_1") (pintype "passive"))
      (node (ref "U2") (pin "17") (pinfunction "(PD0/MISO/PCINT3)PB3_17") (pintype "passive"))
    )
    (net (code "16") (name "/16U2_MOSI") (class "Default")
      (node (ref "J6") (pin "4") (pinfunction "4_4") (pintype "passive"))
      (node (ref "U2") (pin "16") (pinfunction "(PDI/MOSI/PCINT2)PB2_16") (pintype "passive"))
    )
    (net (code "17") (name "/16U2_PB4") (class "Default")
      (node (ref "JP2") (pin "1") (pinfunction "1_1") (pintype "passive"))
      (node (ref "JP3") (pin "2") (pinfunction "2_2") (pintype "passive"))
      (node (ref "U2") (pin "18") (pinfunction "(T1/PCINT4)PB4_18") (pintype "passive"))
    )
    (net (code "18") (name "/16U2_PB5") (class "Default")
      (node (ref "JP2") (pin "3") (pinfunction "3_3") (pintype "passive"))
      (node (ref "U2") (pin "19") (pinfunction "(PCINT5)PB5_19") (pintype "passive"))
    )
    (net (code "19") (name "/16U2_PB6") (class "Default")
      (node (ref "JP2") (pin "2") (pinfunction "2_2") (pintype "passive"))
      (node (ref "U2") (pin "20") (pinfunction "(PCINT6)PB6_20") (pintype "passive"))
    )
    (net (code "20") (name "/16U2_PB7") (class "Default")
      (node (ref "JP2") (pin "4") (pinfunction "4_4") (pintype "passive"))
      (node (ref "U2") (pin "21") (pinfunction "(PCINT7/OC0A/OC1C)PB7_21") (pintype "passive"))
    )
    (net (code "21") (name "/16U2_RESETn") (class "Default")
      (node (ref "JP3") (pin "4") (pinfunction "4_4") (pintype "passive"))
      (node (ref "R5") (pin "1") (pinfunction "1_1") (pintype "passive"))
      (node (ref "U2") (pin "24") (pinfunction "~{RESET}(PC1/DW)_24") (pintype "passive"))
      (node (ref "U5") (pin "4") (pinfunction "4_4") (pintype "passive"))
    )
    (net (code "22") (name "/16U2_RXD") (class "Default")
      (node (ref "R12") (pin "1") (pinfunction "1_1") (pintype "passive"))
      (node (ref "U2") (pin "8") (pinfunction "(RXD1/AIN1/INT2)PD2_8") (pintype "passive"))
    )
    (net (code "23") (name "/16U2_RXD_LED") (class "Default")
      (node (ref "D4") (pin "1") (pinfunction "Cathode_1") (pintype "passive"))
      (node (ref "U2") (pin "10") (pinfunction "(INT5/AIN3)PD4_10") (pintype "passive"))
    )
    (net (code "24") (name "/16U2_SCLK") (class "Default")
      (node (ref "J6") (pin "3") (pinfunction "3_3") (pintype "passive"))
      (node (ref "R6") (pin "2") (pinfunction "2_2") (pintype "passive"))
    )
    (net (code "25") (name "/16U2_SCLK_R") (class "Default")
      (node (ref "R6") (pin "1") (pinfunction "1_1") (pintype "passive"))
      (node (ref "U2") (pin "15") (pinfunction "(SCLK/PCINT1)PB1_15") (pintype "passive"))
    )
    (net (code "26") (name "/16U2_TXD") (class "Default")
      (node (ref "R11") (pin "1") (pinfunction "1_1") (pintype "passive"))
      (node (ref "U2") (pin "9") (pinfunction "(TXD1/INT3)PD3_9") (pintype "passive"))
    )
    (net (code "27") (name "/16U2_TXD_LED") (class "Default")
      (node (ref "D3") (pin "1") (pinfunction "Cathode_1") (pintype "passive"))
      (node (ref "U2") (pin "11") (pinfunction "(XCK/AIN4/PCINT12)PD5_11") (pintype "passive"))
    )
    (net (code "28") (name "/328P_16MHZ_XTAL1") (class "Default")
      (node (ref "C26") (pin "2") (pinfunction "2_2") (pintype "passive"))
      (node (ref "R20") (pin "2") (pinfunction "2_2") (pintype "passive"))
      (node (ref "U1") (pin "9") (pinfunction "XTAL1_9") (pintype "passive"))
      (node (ref "Y1") (pin "2") (pinfunction "2_2") (pintype "passive"))
    )
    (net (code "29") (name "/328P_16MHZ_XTAL2") (class "Default")
      (node (ref "C27") (pin "2") (pinfunction "2_2") (pintype "passive"))
      (node (ref "R20") (pin "1") (pinfunction "1_1") (pintype "passive"))
      (node (ref "U1") (pin "10") (pinfunction "XTAL2_10") (pintype "passive"))
      (node (ref "Y1") (pin "1") (pinfunction "1_1") (pintype "passive"))
    )
    (net (code "30") (name "/328P_AUTORESETn") (class "Default")
      (node (ref "C11") (pin "2") (pinfunction "2_2") (pintype "passive"))
      (node (ref "R21") (pin "1") (pinfunction "1_1") (pintype "passive"))
      (node (ref "U6") (pin "1") (pinfunction "1_1") (pintype "passive"))
    )
    (net (code "31") (name "/328P_BUF_RESETn") (class "Default")
      (node (ref "C32") (pin "2") (pinfunction "2_2") (pintype "passive"))
      (node (ref "R26") (pin "2") (pinfunction "2_2") (pintype "passive"))
      (node (ref "U6") (pin "2") (pinfunction "2_2") (pintype "passive"))
    )
    (net (code "32") (name "/328P_RESETn") (class "Default")
      (node (ref "J1") (pin "3") (pinfunction "3_3") (pintype "passive"))
      (node (ref "J5") (pin "5") (pinfunction "5_5") (pintype "passive"))
      (node (ref "JP3") (pin "1") (pinfunction "1_1") (pintype "passive"))
      (node (ref "R17") (pin "1") (pinfunction "1_1") (pintype "passive"))
      (node (ref "U1") (pin "1") (pinfunction "~{RESET}_1") (pintype "passive"))
      (node (ref "U6") (pin "4") (pinfunction "4_4") (pintype "passive"))
    )
    (net (code "33") (name "/AD0") (class "Default")
      (node (ref "J2") (pin "1") (pinfunction "1_1") (pintype "passive"))
      (node (ref "U1") (pin "23") (pinfunction "(ADC0)PC0)_23") (pintype "passive"))
    )
    (net (code "34") (name "/AD1") (class "Default")
      (node (ref "J2") (pin "2") (pinfunction "2_2") (pintype "passive"))
      (node (ref "U1") (pin "24") (pinfunction "(ADC1)PC1_24") (pintype "passive"))
    )
    (net (code "35") (name "/AD2") (class "Default")
      (node (ref "J2") (pin "3") (pinfunction "3_3") (pintype "passive"))
      (node (ref "U1") (pin "25") (pinfunction "(ADC2)PC2_25") (pintype "passive"))
    )
    (net (code "36") (name "/AD3") (class "Default")
      (node (ref "J2") (pin "4") (pinfunction "4_4") (pintype "passive"))
      (node (ref "U1") (pin "26") (pinfunction "(ADC3)PC3_26") (pintype "passive"))
    )
    (net (code "37") (name "/AD4{slash}SDA") (class "Default")
      (node (ref "J2") (pin "5") (pinfunction "5_5") (pintype "passive"))
      (node (ref "J4") (pin "9") (pinfunction "9_9") (pintype "passive"))
      (node (ref "U1") (pin "27") (pinfunction "(ADC4)PC4_27") (pintype "passive"))
    )
    (net (code "38") (name "/AD5{slash}SCL") (class "Default")
      (node (ref "J2") (pin "6") (pinfunction "6_6") (pintype "passive"))
      (node (ref "J4") (pin "10") (pinfunction "10_10") (pintype "passive"))
      (node (ref "U1") (pin "28") (pinfunction "(ADC5)PC5_28") (pintype "passive"))
    )
    (net (code "39") (name "/BUTTON_RESETn") (class "Default")
      (node (ref "R22") (pin "1") (pinfunction "1_1") (pintype "passive"))
      (node (ref "SW1") (pin "3") (pinfunction "3_3") (pintype "passive"))
      (node (ref "SW1") (pin "4") (pinfunction "4_4") (pintype "passive"))
    )
    (net (code "40") (name "/CON_USB_N") (class "Default")
      (node (ref "J7") (pin "2") (pinfunction "2_2") (pintype "passive"))
      (node (ref "R7") (pin "1") (pinfunction "1_1") (pintype "passive"))
      (node (ref "Z2") (pin "2") (pinfunction "2_2") (pintype "passive"))
    )
    (net (code "41") (name "/CON_USB_P") (class "Default")
      (node (ref "J7") (pin "3") (pinfunction "3_3") (pintype "passive"))
      (node (ref "R8") (pin "1") (pinfunction "1_1") (pintype "passive"))
      (node (ref "Z1") (pin "2") (pinfunction "2_2") (pintype "passive"))
    )
    (net (code "42") (name "/IO0") (class "Default")
      (node (ref "J3") (pin "1") (pinfunction "1_1") (pintype "passive"))
      (node (ref "R11") (pin "2") (pinfunction "2_2") (pintype "passive"))
      (node (ref "U1") (pin "2") (pinfunction "(RXD)PD0_2") (pintype "passive"))
    )
    (net (code "43") (name "/IO1") (class "Default")
      (node (ref "J3") (pin "2") (pinfunction "2_2") (pintype "passive"))
      (node (ref "R12") (pin "2") (pinfunction "2_2") (pintype "passive"))
      (node (ref "U1") (pin "3") (pinfunction "(TXD)PD1_3") (pintype "passive"))
    )
    (net (code "44") (name "/IO2") (class "Default")
      (node (ref "J3") (pin "3") (pinfunction "3_3") (pintype "passive"))
      (node (ref "U1") (pin "4") (pinfunction "(INT0)PD2_4") (pintype "passive"))
    )
    (net (code "45") (name "/IO3") (class "Default")
      (node (ref "J3") (pin "4") (pinfunction "4_4") (pintype "passive"))
      (node (ref "U1") (pin "5") (pinfunction "(INT1)PD3_5") (pintype "passive"))
    )
    (net (code "46") (name "/IO4") (class "Default")
      (node (ref "J3") (pin "5") (pinfunction "5_5") (pintype "passive"))
      (node (ref "U1") (pin "6") (pinfunction "(T0)PD4_6") (pintype "passive"))
    )
    (net (code "47") (name "/IO5") (class "Default")
      (node (ref "J3") (pin "6") (pinfunction "6_6") (pintype "passive"))
      (node (ref "U1") (pin "11") (pinfunction "(T1)PD5_11") (pintype "passive"))
    )
    (net (code "48") (name "/IO6") (class "Default")
      (node (ref "J3") (pin "7") (pinfunction "7_7") (pintype "passive"))
      (node (ref "U1") (pin "12") (pinfunction "(AIN0)PD6_12") (pintype "passive"))
    )
    (net (code "49") (name "/IO7") (class "Default")
      (node (ref "J3") (pin "8") (pinfunction "8_8") (pintype "passive"))
      (node (ref "U1") (pin "13") (pinfunction "(AIN1)PD7_13") (pintype "passive"))
    )
    (net (code "50") (name "/IO8") (class "Default")
      (node (ref "J4") (pin "1") (pinfunction "1_1") (pintype "passive"))
      (node (ref "R25") (pin "1") (pinfunction "1_1") (pintype "passive"))
      (node (ref "U1") (pin "14") (pinfunction "(ICP)PB0_14") (pintype "passive"))
    )
    (net (code "51") (name "/IO9") (class "Default")
      (node (ref "J4") (pin "2") (pinfunction "2_2") (pintype "passive"))
      (node (ref "U1") (pin "15") (pinfunction "(OC1)PB1_15") (pintype "passive"))
    )
    (net (code "52") (name "/MISO") (class "Default")
      (node (ref "J4") (pin "5") (pinfunction "5_5") (pintype "passive"))
      (node (ref "J5") (pin "1") (pinfunction "1_1") (pintype "passive"))
      (node (ref "U1") (pin "18") (pinfunction "(MISO)PB4_18") (pintype "passive"))
    )
    (net (code "53") (name "/MOSI") (class "Default")
      (node (ref "J4") (pin "4") (pinfunction "4_4") (pintype "passive"))
      (node (ref "J5") (pin "4") (pinfunction "4_4") (pintype "passive"))
      (node (ref "U1") (pin "17") (pinfunction "(MOSI)PB3_17") (pintype "passive"))
    )
    (net (code "54") (name "/SCK") (class "Default")
      (node (ref "J4") (pin "6") (pinfunction "6_6") (pintype "passive"))
      (node (ref "J5") (pin "3") (pinfunction "3_3") (pintype "passive"))
      (node (ref "R16") (pin "2") (pinfunction "2_2") (pintype "passive"))
      (node (ref "U4") (pin "1") (pinfunction "1_1") (pintype "passive"))
      (node (ref "U4") (pin "2") (pinfunction "2_2") (pintype "passive"))
    )
    (net (code "55") (name "/SCK_R") (class "Default")
      (node (ref "R16") (pin "1") (pinfunction "1_1") (pintype "passive"))
      (node (ref "U1") (pin "19") (pinfunction "(SCK)PB5_19") (pintype "passive"))
    )
    (net (code "56") (name "/SS") (class "Default")
      (node (ref "J4") (pin "3") (pinfunction "3_3") (pintype "passive"))
      (node (ref "U1") (pin "16") (pinfunction "(SS)PB2_16") (pintype "passive"))
    )
    (net (code "57") (name "/USB_N") (class "Default")
      (node (ref "R7") (pin "2") (pinfunction "2_2") (pintype "passive"))
      (node (ref "U2") (pin "30") (pinfunction "D-_30") (pintype "passive"))
    )
    (net (code "58") (name "/USB_P") (class "Default")
      (node (ref "R8") (pin "2") (pinfunction "2_2") (pintype "passive"))
      (node (ref "U2") (pin "29") (pinfunction "D+_29") (pintype "passive"))
    )
    (net (code "59") (name "/USER_BUTTON") (class "Default")
      (node (ref "R23") (pin "1") (pinfunction "1_1") (pintype "passive"))
      (node (ref "R27") (pin "1") (pinfunction "1_1") (pintype "passive"))
      (node (ref "SW2") (pin "3") (pinfunction "3_3") (pintype "passive"))
      (node (ref "SW2") (pin "4") (pinfunction "4_4") (pintype "passive"))
    )
    (net (code "60") (name "/USER_BUTTON_BUF") (class "Default")
      (node (ref "C31") (pin "2") (pinfunction "2_2") (pintype "passive"))
      (node (ref "R27") (pin "2") (pinfunction "2_2") (pintype "passive"))
      (node (ref "U7") (pin "1") (pinfunction "1_1") (pintype "passive"))
      (node (ref "U7") (pin "2") (pinfunction "2_2") (pintype "passive"))
    )
    (net (code "61") (name "Net-(C11-Pad1)") (class "Default")
      (node (ref "C11") (pin "1") (pinfunction "1_1") (pintype "passive"))
      (node (ref "JP1") (pin "1") (pinfunction "1_1") (pintype "passive"))
    )
    (net (code "62") (name "Net-(D1-Anode)") (class "Default")
      (node (ref "D1") (pin "2") (pinfunction "Anode_2") (pintype "passive"))
      (node (ref "R19") (pin "1") (pinfunction "1_1") (pintype "passive"))
    )
    (net (code "63") (name "Net-(D2-Anode)") (class "Default")
      (node (ref "D2") (pin "2") (pinfunction "Anode_2") (pintype "passive"))
      (node (ref "R18") (pin "1") (pinfunction "1_1") (pintype "passive"))
    )
    (net (code "64") (name "Net-(D2-Cathode)") (class "Default")
      (node (ref "D2") (pin "1") (pinfunction "Cathode_1") (pintype "passive"))
      (node (ref "U4") (pin "4") (pinfunction "4_4") (pintype "passive"))
    )
    (net (code "65") (name "Net-(D3-Anode)") (class "Default")
      (node (ref "D3") (pin "2") (pinfunction "Anode_2") (pintype "passive"))
      (node (ref "R2") (pin "1") (pinfunction "1_1") (pintype "passive"))
    )
    (net (code "66") (name "Net-(D4-Anode)") (class "Default")
      (node (ref "D4") (pin "2") (pinfunction "Anode_2") (pintype "passive"))
      (node (ref "R3") (pin "1") (pinfunction "1_1") (pintype "passive"))
    )
    (net (code "67") (name "Net-(D5-Anode)") (class "Default")
      (node (ref "D5") (pin "2") (pinfunction "Anode_2") (pintype "passive"))
      (node (ref "R28") (pin "1") (pinfunction "1_1") (pintype "passive"))
    )
    (net (code "68") (name "Net-(D6-Anode)") (class "Default")
      (node (ref "D6") (pin "2") (pinfunction "Anode_2") (pintype "passive"))
      (node (ref "R26") (pin "1") (pinfunction "1_1") (pintype "passive"))
    )
    (net (code "69") (name "Net-(J7-Pad4)") (class "Default")
      (node (ref "J7") (pin "4") (pinfunction "4_4") (pintype "passive"))
      (node (ref "R9") (pin "1") (pinfunction "1_1") (pintype "passive"))
    )
    (net (code "70") (name "Net-(JP1-Pad3)") (class "Default")
      (node (ref "JP1") (pin "3") (pinfunction "3_3") (pintype "passive"))
      (node (ref "R13") (pin "2") (pinfunction "2_2") (pintype "passive"))
    )
    (net (code "71") (name "Net-(R25-Pad2)") (class "Default")
      (node (ref "R25") (pin "2") (pinfunction "2_2") (pintype "passive"))
      (node (ref "U7") (pin "4") (pinfunction "4_4") (pintype "passive"))
    )
    (net (code "72") (name "Net-(U1-AREF)") (class "Default")
      (node (ref "C24") (pin "1") (pinfunction "1_1") (pintype "passive"))
      (node (ref "U1") (pin "21") (pinfunction "AREF_21") (pintype "passive"))
    )
    (net (code "73") (name "unconnected-(J1-Pad1)") (class "Default")
      (node (ref "J1") (pin "1") (pinfunction "1_1") (pintype "passive+no_connect"))
    )
    (net (code "74") (name "unconnected-(J1-Pad8)") (class "Default")
      (node (ref "J1") (pin "8") (pinfunction "8_8") (pintype "passive+no_connect"))
    )
    (net (code "75") (name "unconnected-(MH4-Pad1)") (class "Default")
      (node (ref "MH4") (pin "1") (pinfunction "1_1") (pintype "passive+no_connect"))
    )
    (net (code "76") (name "unconnected-(R24-Pad1)") (class "Default")
      (node (ref "R24") (pin "1") (pinfunction "1_1") (pintype "passive"))
    )
    (net (code "77") (name "unconnected-(U2-(AIN0{slash}INT1)PD1-Pad7)") (class "Default")
      (node (ref "U2") (pin "7") (pinfunction "(AIN0/INT1)PD1_7") (pintype "passive+no_connect"))
    )
    (net (code "78") (name "unconnected-(U2-(AIN2{slash}PCINT11)PC2-Pad5)") (class "Default")
      (node (ref "U2") (pin "5") (pinfunction "(AIN2/PCINT11)PC2_5") (pintype "passive+no_connect"))
    )
    (net (code "79") (name "unconnected-(U2-(INT4{slash}ICP1{slash}CLK0)PC7-Pad22)") (class "Default")
      (node (ref "U2") (pin "22") (pinfunction "(INT4/ICP1/CLK0)PC7_22") (pintype "passive+no_connect"))
    )
    (net (code "80") (name "unconnected-(U2-(OC0B{slash}INT0)PD0-Pad6)") (class "Default")
      (node (ref "U2") (pin "6") (pinfunction "(OC0B/INT0)PD0_6") (pintype "passive+no_connect"))
    )
    (net (code "81") (name "unconnected-(U2-(OC1A{slash}PCINT8)PC6-Pad23)") (class "Default")
      (node (ref "U2") (pin "23") (pinfunction "(OC1A/PCINT8)PC6_23") (pintype "passive+no_connect"))
    )
    (net (code "82") (name "unconnected-(U2-(PCINT9{slash}OC1B)PC5-Pad25)") (class "Default")
      (node (ref "U2") (pin "25") (pinfunction "(PCINT9/OC1B)PC5_25") (pintype "passive+no_connect"))
    )
    (net (code "83") (name "unconnected-(U2-(PCINT10)PC4-Pad26)") (class "Default")
      (node (ref "U2") (pin "26") (pinfunction "(PCINT10)PC4_26") (pintype "passive+no_connect"))
    )
    (net (code "84") (name "unconnected-(U2-(RTS{slash}AIN5{slash}INT6)PD6-Pad12)") (class "Default")
      (node (ref "U2") (pin "12") (pinfunction "(RTS/AIN5/INT6)PD6_12") (pintype "passive"))
    )
    (net (code "85") (name "unconnected-(U2-(SS{slash}PCINT0)PB0-Pad14)") (class "Default")
      (node (ref "U2") (pin "14") (pinfunction "(SS/PCINT0)PB0_14") (pintype "passive+no_connect"))
    )
  )
)
